# IO_Valve_testing.net
KiCad netlist of a schematic drawn in EAGLE
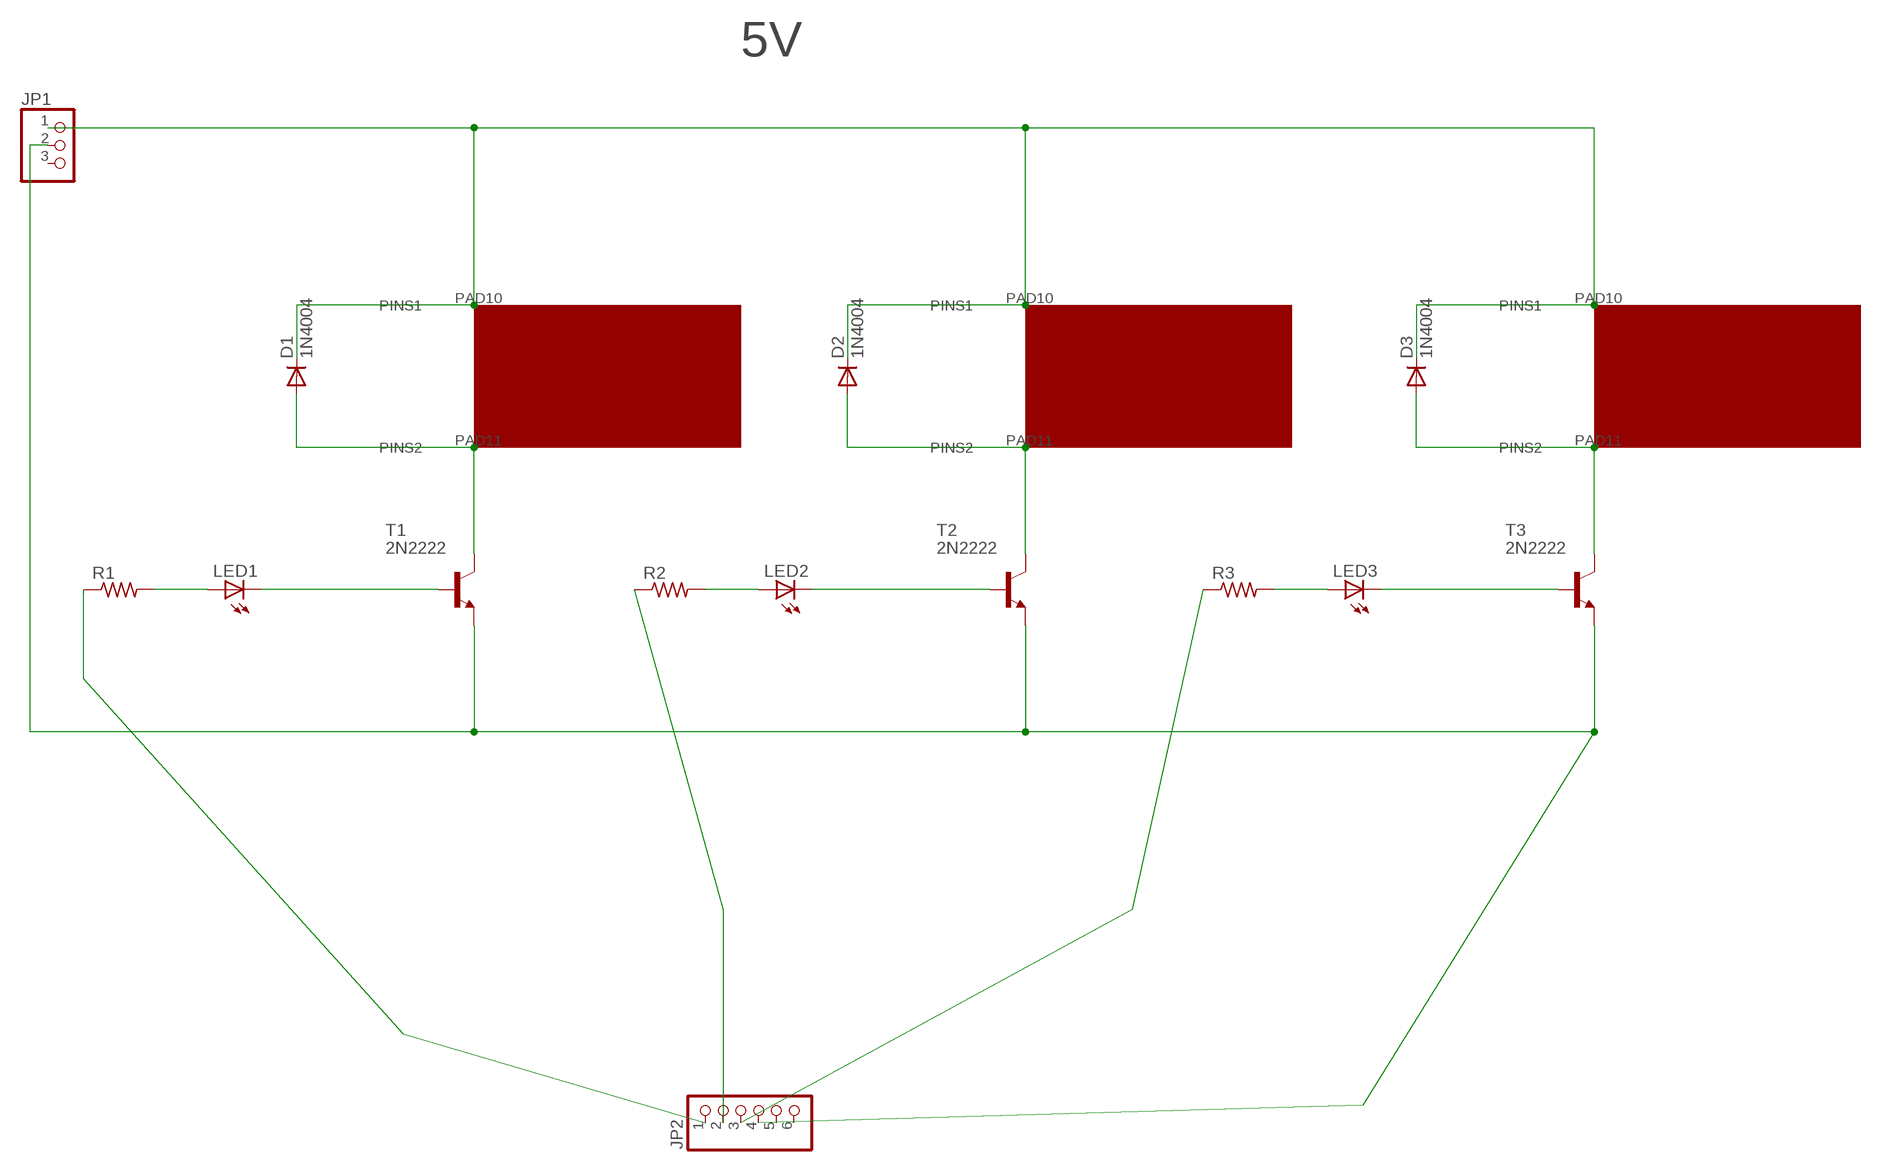
[diagram p0: schematic, sheet 1]

(export (version "E")
  (design (tool "Eeschema 10.0.6"))
  (components
    (comp (ref "D1")
      (value "1N4004")
      (footprint "eagle-import:DO41-10")
      (libsource (lib "eagle-import") (part "1N4004"))
    )
    (comp (ref "D2")
      (value "1N4004")
      (footprint "eagle-import:DO41-10")
      (libsource (lib "eagle-import") (part "1N4004"))
    )
    (comp (ref "D3")
      (value "1N4004")
      (footprint "eagle-import:DO41-10")
      (libsource (lib "eagle-import") (part "1N4004"))
    )
    (comp (ref "JP1")
      (value "PINHD-1X3")
      (footprint "eagle-import:1X03")
      (libsource (lib "eagle-import") (part "PINHD-1X3"))
    )
    (comp (ref "JP2")
      (value "PINHD-1X6")
      (footprint "eagle-import:1X06")
      (libsource (lib "eagle-import") (part "PINHD-1X6"))
    )
    (comp (ref "LED1")
      (value "LED5MM")
      (footprint "eagle-import:LED5MM")
      (libsource (lib "eagle-import") (part "LED5MM"))
    )
    (comp (ref "LED2")
      (value "LED5MM")
      (footprint "eagle-import:LED5MM")
      (libsource (lib "eagle-import") (part "LED5MM"))
    )
    (comp (ref "LED3")
      (value "LED5MM")
      (footprint "eagle-import:LED5MM")
      (libsource (lib "eagle-import") (part "LED5MM"))
    )
    (comp (ref "R1")
      (value "R-US_0207/10")
      (footprint "eagle-import:0207_10")
      (libsource (lib "eagle-import") (part "R-US_0207/10"))
    )
    (comp (ref "R2")
      (value "R-US_0207/10")
      (footprint "eagle-import:0207_10")
      (libsource (lib "eagle-import") (part "R-US_0207/10"))
    )
    (comp (ref "R3")
      (value "R-US_0207/10")
      (footprint "eagle-import:0207_10")
      (libsource (lib "eagle-import") (part "R-US_0207/10"))
    )
    (comp (ref "T1")
      (value "2N2222")
      (footprint "eagle-import:TO92-EBC-OVAL")
      (libsource (lib "eagle-import") (part "2N2222"))
    )
    (comp (ref "T2")
      (value "2N2222")
      (footprint "eagle-import:TO92-EBC-OVAL")
      (libsource (lib "eagle-import") (part "2N2222"))
    )
    (comp (ref "T3")
      (value "2N2222")
      (footprint "eagle-import:TO92-EBC-OVAL")
      (libsource (lib "eagle-import") (part "2N2222"))
    )
    (comp (ref "U$1")
      (value "VALVE")
      (footprint "eagle-import:VALVTEST2")
      (libsource (lib "eagle-import") (part "VALVE"))
    )
    (comp (ref "U$2")
      (value "VALVE")
      (footprint "eagle-import:VALVTEST2")
      (libsource (lib "eagle-import") (part "VALVE"))
    )
    (comp (ref "U$3")
      (value "VALVE")
      (footprint "eagle-import:VALVTEST2")
      (libsource (lib "eagle-import") (part "VALVE"))
    )
  )
  (nets
    (net (code "1") (name "/5V") (class "Default")
      (node (ref "D1") (pin "C") (pinfunction "C_C") (pintype "passive"))
      (node (ref "D2") (pin "C") (pinfunction "C_C") (pintype "passive"))
      (node (ref "D3") (pin "C") (pinfunction "C_C") (pintype "passive"))
      (node (ref "JP1") (pin "1") (pinfunction "1_1") (pintype "passive"))
      (node (ref "U$1") (pin "PAD10") (pinfunction "PINS1_PAD10") (pintype "bidirectional"))
      (node (ref "U$2") (pin "PAD10") (pinfunction "PINS1_PAD10") (pintype "bidirectional"))
      (node (ref "U$3") (pin "PAD10") (pinfunction "PINS1_PAD10") (pintype "bidirectional"))
    )
    (net (code "2") (name "Net-(JP1-Pad2)") (class "Default")
      (node (ref "JP1") (pin "2") (pinfunction "2_2") (pintype "passive"))
      (node (ref "JP2") (pin "4") (pinfunction "4_4") (pintype "passive"))
      (node (ref "T1") (pin "E") (pinfunction "E_E") (pintype "passive"))
      (node (ref "T2") (pin "E") (pinfunction "E_E") (pintype "passive"))
      (node (ref "T3") (pin "E") (pinfunction "E_E") (pintype "passive"))
    )
    (net (code "3") (name "Net-(JP2-Pad1)") (class "Default")
      (node (ref "JP2") (pin "1") (pinfunction "1_1") (pintype "passive"))
      (node (ref "R1") (pin "1") (pinfunction "1_1") (pintype "passive"))
    )
    (net (code "4") (name "Net-(JP2-Pad2)") (class "Default")
      (node (ref "JP2") (pin "2") (pinfunction "2_2") (pintype "passive"))
      (node (ref "R2") (pin "1") (pinfunction "1_1") (pintype "passive"))
    )
    (net (code "5") (name "Net-(JP2-Pad3)") (class "Default")
      (node (ref "JP2") (pin "3") (pinfunction "3_3") (pintype "passive"))
      (node (ref "R3") (pin "1") (pinfunction "1_1") (pintype "passive"))
    )
    (net (code "6") (name "Net-(LED1-C)") (class "Default")
      (node (ref "LED1") (pin "K") (pinfunction "C_K") (pintype "passive"))
      (node (ref "T1") (pin "B") (pinfunction "B_B") (pintype "passive"))
    )
    (net (code "7") (name "Net-(LED1-PadA)") (class "Default")
      (node (ref "LED1") (pin "A") (pinfunction "A_A") (pintype "passive"))
      (node (ref "R1") (pin "2") (pinfunction "2_2") (pintype "passive"))
    )
    (net (code "8") (name "Net-(LED2-C)") (class "Default")
      (node (ref "LED2") (pin "K") (pinfunction "C_K") (pintype "passive"))
      (node (ref "T2") (pin "B") (pinfunction "B_B") (pintype "passive"))
    )
    (net (code "9") (name "Net-(LED2-PadA)") (class "Default")
      (node (ref "LED2") (pin "A") (pinfunction "A_A") (pintype "passive"))
      (node (ref "R2") (pin "2") (pinfunction "2_2") (pintype "passive"))
    )
    (net (code "10") (name "Net-(LED3-C)") (class "Default")
      (node (ref "LED3") (pin "K") (pinfunction "C_K") (pintype "passive"))
      (node (ref "T3") (pin "B") (pinfunction "B_B") (pintype "passive"))
    )
    (net (code "11") (name "Net-(LED3-PadA)") (class "Default")
      (node (ref "LED3") (pin "A") (pinfunction "A_A") (pintype "passive"))
      (node (ref "R3") (pin "2") (pinfunction "2_2") (pintype "passive"))
    )
    (net (code "12") (name "Net-(U$1-PINS2)") (class "Default")
      (node (ref "D1") (pin "A") (pinfunction "A_A") (pintype "passive"))
      (node (ref "T1") (pin "C") (pinfunction "C_C") (pintype "passive"))
      (node (ref "U$1") (pin "PAD11") (pinfunction "PINS2_PAD11") (pintype "bidirectional"))
    )
    (net (code "13") (name "Net-(U$2-PINS2)") (class "Default")
      (node (ref "D2") (pin "A") (pinfunction "A_A") (pintype "passive"))
      (node (ref "T2") (pin "C") (pinfunction "C_C") (pintype "passive"))
      (node (ref "U$2") (pin "PAD11") (pinfunction "PINS2_PAD11") (pintype "bidirectional"))
    )
    (net (code "14") (name "Net-(U$3-PINS2)") (class "Default")
      (node (ref "D3") (pin "A") (pinfunction "A_A") (pintype "passive"))
      (node (ref "T3") (pin "C") (pinfunction "C_C") (pintype "passive"))
      (node (ref "U$3") (pin "PAD11") (pinfunction "PINS2_PAD11") (pintype "bidirectional"))
    )
    (net (code "15") (name "unconnected-(JP1-Pad3)") (class "Default")
      (node (ref "JP1") (pin "3") (pinfunction "3_3") (pintype "passive"))
    )
    (net (code "16") (name "unconnected-(JP2-Pad5)") (class "Default")
      (node (ref "JP2") (pin "5") (pinfunction "5_5") (pintype "passive"))
    )
    (net (code "17") (name "unconnected-(JP2-Pad6)") (class "Default")
      (node (ref "JP2") (pin "6") (pinfunction "6_6") (pintype "passive"))
    )
  )
)
